# RN2483_breakout.net
KiCad netlist of a schematic drawn in Altium Designer
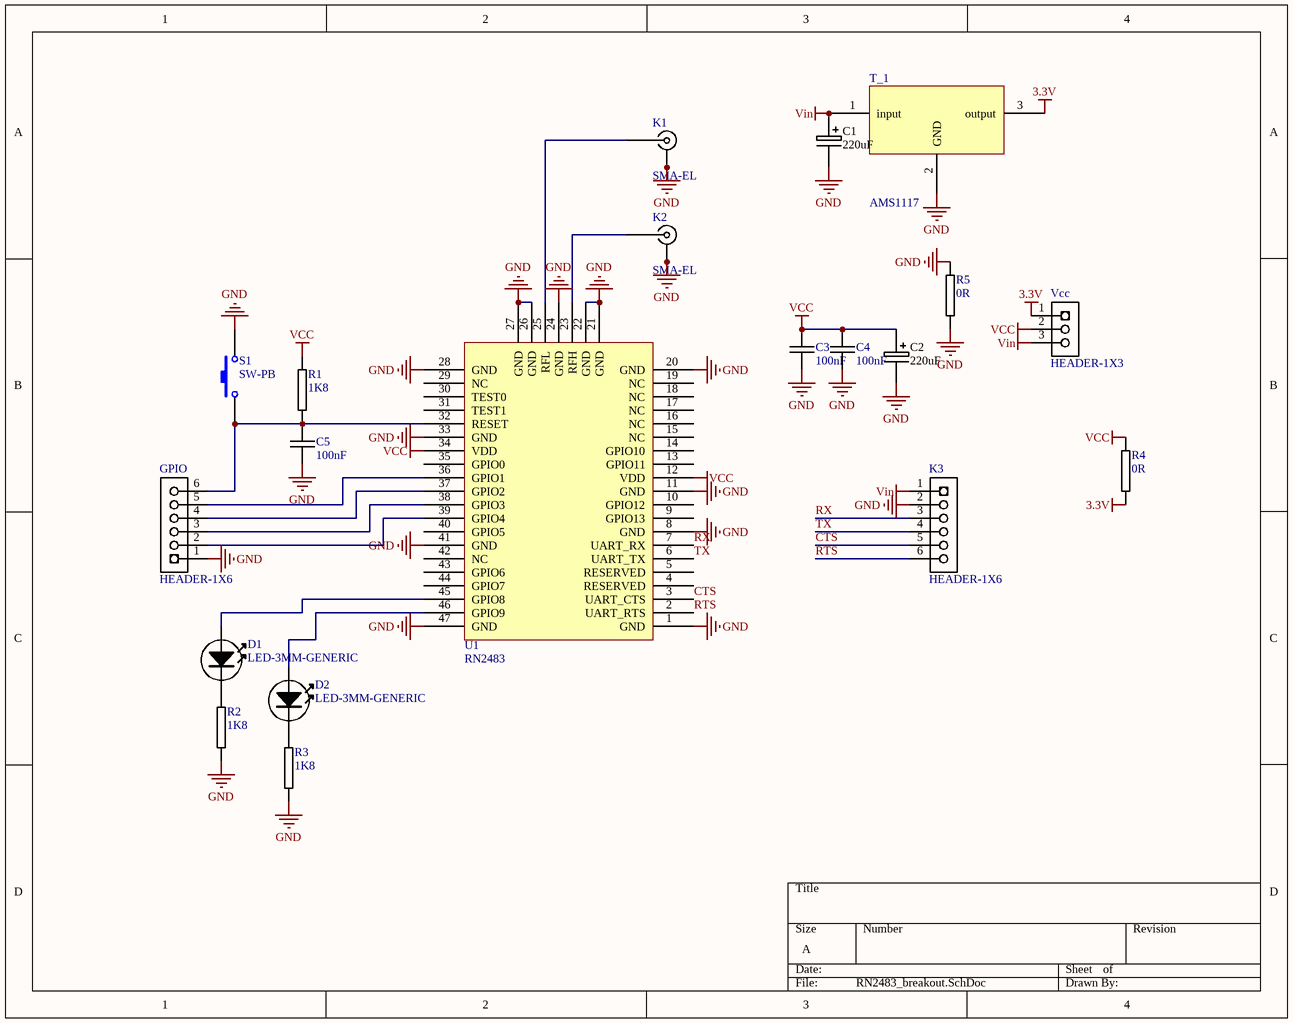
[diagram p0: RN2483_breakout.SchDoc]

(export (version "E")
  (design (tool "Eeschema 10.0.6"))
  (components
    (comp (ref "C1")
      (value "220uF")
      (footprint "TANTAL_SIZEA")
      (description "CAPACITOR POLARISED")
      (libsource (lib "vh_altium_library") (part "220UF-5MM"))
    )
    (comp (ref "C2")
      (value "220uF")
      (footprint "TANTAL_SIZEA")
      (description "CAPACITOR POLARISED")
      (libsource (lib "vh_altium_library") (part "220UF-5MM"))
    )
    (comp (ref "C3")
      (value "100nF")
      (footprint "0805C-GENERIC")
      (description "CAPACITOR 0805 CERAMIC")
      (fields (field (name "TOLERANCE") "±20%") (field (name "MANUFACTURER") "Panasonic - ECG"))
      (libsource (lib "vh_altium_library") (part "0805C-10UF-6V3-X5R-PAN"))
    )
    (comp (ref "C4")
      (value "100nF")
      (footprint "0805C-GENERIC")
      (description "CAPACITOR 0805 CERAMIC")
      (fields (field (name "TOLERANCE") "±20%") (field (name "MANUFACTURER") "Panasonic - ECG"))
      (libsource (lib "vh_altium_library") (part "0805C-10UF-6V3-X5R-PAN"))
    )
    (comp (ref "C5")
      (value "100nF")
      (footprint "0805C-GENERIC")
      (description "CAPACITOR 0805 CERAMIC")
      (fields (field (name "TOLERANCE") "±20%") (field (name "MANUFACTURER") "Panasonic - ECG"))
      (libsource (lib "vh_altium_library") (part "0805C-10UF-6V3-X5R-PAN"))
    )
    (comp (ref "D1")
      (value "LED-3MM-GENERIC")
      (footprint "0805R-GENERIC")
      (description "GENERIC LED 3MM")
      (libsource (lib "vh_altium_library") (part "LED-3MM-GENERIC"))
    )
    (comp (ref "D2")
      (value "LED-3MM-GENERIC")
      (footprint "0805R-GENERIC")
      (description "GENERIC LED 3MM")
      (libsource (lib "vh_altium_library") (part "LED-3MM-GENERIC"))
    )
    (comp (ref "GPIO")
      (value "HEADER-1X6")
      (footprint "HEADER-1X6")
      (libsource (lib "vh_altium_library") (part "HEADER-1X6"))
    )
    (comp (ref "K1")
      (value "SMA-EL")
      (footprint "SMA-ENDLAUNCH")
      (description "SMA THREADED RF CONNECTOR VERTICAL")
      (libsource (lib "vh_altium_library") (part "SMA-EL"))
    )
    (comp (ref "K2")
      (value "SMA-EL")
      (footprint "SMA-ENDLAUNCH")
      (description "SMA THREADED RF CONNECTOR VERTICAL")
      (libsource (lib "vh_altium_library") (part "SMA-EL"))
    )
    (comp (ref "K3")
      (value "HEADER-1X6")
      (footprint "HEADER-1X6")
      (libsource (lib "vh_altium_library") (part "HEADER-1X6"))
    )
    (comp (ref "R1")
      (value "1K8")
      (footprint "0805R-1K8")
      (description "RESISTOR 0805 1/4 WATT THIN FILM")
      (libsource (lib "vh_altium_library") (part "0805R-1K8"))
    )
    (comp (ref "R2")
      (value "1K8")
      (footprint "0805R-1K8")
      (description "RESISTOR 0805 1/4 WATT THIN FILM")
      (libsource (lib "vh_altium_library") (part "0805R-1K8"))
    )
    (comp (ref "R3")
      (value "1K8")
      (footprint "0805R-1K8")
      (description "RESISTOR 0805 1/4 WATT THIN FILM")
      (libsource (lib "vh_altium_library") (part "0805R-1K8"))
    )
    (comp (ref "R4")
      (value "0R")
      (footprint "0805R-GENERIC")
      (description "RESISTOR 0805 1 WATT")
      (libsource (lib "vh_altium_library") (part "0805R-0R"))
    )
    (comp (ref "R5")
      (value "0R")
      (footprint "0805R-GENERIC")
      (description "RESISTOR 0805 1 WATT")
      (libsource (lib "vh_altium_library") (part "0805R-0R"))
    )
    (comp (ref "S1")
      (value "SW-PB")
      (footprint "SW")
      (description "Switch")
      (fields (field (name "PUBLISHER") "Altium Limited"))
      (libsource (lib "Miscellaneous Devices") (part "SW-PB"))
    )
    (comp (ref "T_1")
      (value "AMS1117")
      (footprint "SOT-223B_M")
      (description "Voltage Regulator")
      (libsource (lib "MAX4644") (part "LM7815"))
    )
    (comp (ref "U1")
      (value "RN2483")
      (footprint "RN2483")
      (description "RN2483 - Microchip")
      (libsource (lib "RN2483_breakout_lib") (part "RN2483"))
    )
    (comp (ref "Vcc")
      (value "HEADER-1X3")
      (footprint "HEADER-1X3")
      (libsource (lib "vh_altium_library") (part "HEADER-1X3"))
    )
  )
  (nets
    (net (code "1") (name "/CTS") (class "Default")
      (node (ref "K3") (pin "5") (pintype "passive"))
      (node (ref "U1") (pin "3") (pinfunction "UART_CTS_3") (pintype "passive"))
    )
    (net (code "2") (name "/RTS") (class "Default")
      (node (ref "K3") (pin "6") (pintype "passive"))
      (node (ref "U1") (pin "2") (pinfunction "UART_RTS_2") (pintype "passive"))
    )
    (net (code "3") (name "/RX") (class "Default")
      (node (ref "K3") (pin "3") (pintype "passive"))
      (node (ref "U1") (pin "7") (pinfunction "UART_RX_7") (pintype "passive"))
    )
    (net (code "4") (name "/TX") (class "Default")
      (node (ref "K3") (pin "4") (pintype "passive"))
      (node (ref "U1") (pin "6") (pinfunction "UART_TX_6") (pintype "passive"))
    )
    (net (code "5") (name "3.3V") (class "Default")
      (node (ref "R4") (pin "2") (pintype "passive"))
      (node (ref "T_1") (pin "3") (pinfunction "output_3") (pintype "passive"))
      (node (ref "Vcc") (pin "1") (pintype "passive"))
    )
    (net (code "6") (name "GND") (class "Default")
      (node (ref "C1") (pin "-") (pinfunction "-_-") (pintype "passive"))
      (node (ref "C2") (pin "-") (pinfunction "-_-") (pintype "passive"))
      (node (ref "C3") (pin "2") (pintype "passive"))
      (node (ref "C4") (pin "2") (pintype "passive"))
      (node (ref "C5") (pin "2") (pintype "passive"))
      (node (ref "GPIO") (pin "1") (pintype "passive"))
      (node (ref "K1") (pin "2") (pinfunction "2_2") (pintype "passive"))
      (node (ref "K1") (pin "3") (pinfunction "3_3") (pintype "passive"))
      (node (ref "K1") (pin "4") (pinfunction "4_4") (pintype "passive"))
      (node (ref "K1") (pin "5") (pinfunction "5_5") (pintype "passive"))
      (node (ref "K2") (pin "2") (pinfunction "2_2") (pintype "passive"))
      (node (ref "K2") (pin "3") (pinfunction "3_3") (pintype "passive"))
      (node (ref "K2") (pin "4") (pinfunction "4_4") (pintype "passive"))
      (node (ref "K2") (pin "5") (pinfunction "5_5") (pintype "passive"))
      (node (ref "K3") (pin "2") (pintype "passive"))
      (node (ref "R2") (pin "2") (pintype "passive"))
      (node (ref "R3") (pin "2") (pintype "passive"))
      (node (ref "R5") (pin "1") (pintype "passive"))
      (node (ref "R5") (pin "2") (pintype "passive"))
      (node (ref "S1") (pin "2") (pinfunction "2_2") (pintype "passive"))
      (node (ref "T_1") (pin "2") (pinfunction "GND_2") (pintype "passive"))
      (node (ref "U1") (pin "1") (pinfunction "GND_1") (pintype "passive"))
      (node (ref "U1") (pin "11") (pinfunction "GND_11") (pintype "passive"))
      (node (ref "U1") (pin "20") (pinfunction "GND_20") (pintype "passive"))
      (node (ref "U1") (pin "21") (pinfunction "GND_21") (pintype "passive"))
      (node (ref "U1") (pin "22") (pinfunction "GND_22") (pintype "passive"))
      (node (ref "U1") (pin "24") (pinfunction "GND_24") (pintype "passive"))
      (node (ref "U1") (pin "26") (pinfunction "GND_26") (pintype "passive"))
      (node (ref "U1") (pin "27") (pinfunction "GND_27") (pintype "passive"))
      (node (ref "U1") (pin "28") (pinfunction "GND_28") (pintype "passive"))
      (node (ref "U1") (pin "33") (pinfunction "GND_33") (pintype "passive"))
      (node (ref "U1") (pin "41") (pinfunction "GND_41") (pintype "passive"))
      (node (ref "U1") (pin "47") (pinfunction "GND_47") (pintype "passive"))
      (node (ref "U1") (pin "8") (pinfunction "GND_8") (pintype "passive"))
    )
    (net (code "7") (name "Net-(D1-PadK)") (class "Default")
      (node (ref "D1") (pin "K") (pintype "passive"))
      (node (ref "R2") (pin "1") (pintype "passive"))
    )
    (net (code "8") (name "Net-(D2-PadK)") (class "Default")
      (node (ref "D2") (pin "K") (pintype "passive"))
      (node (ref "R3") (pin "1") (pintype "passive"))
    )
    (net (code "9") (name "Net-(U1-GPIO1)") (class "Default")
      (node (ref "GPIO") (pin "5") (pintype "passive"))
      (node (ref "U1") (pin "36") (pinfunction "GPIO1_36") (pintype "passive"))
    )
    (net (code "10") (name "Net-(U1-GPIO2)") (class "Default")
      (node (ref "GPIO") (pin "4") (pintype "passive"))
      (node (ref "U1") (pin "37") (pinfunction "GPIO2_37") (pintype "passive"))
    )
    (net (code "11") (name "Net-(U1-GPIO3)") (class "Default")
      (node (ref "GPIO") (pin "3") (pintype "passive"))
      (node (ref "U1") (pin "38") (pinfunction "GPIO3_38") (pintype "passive"))
    )
    (net (code "12") (name "Net-(U1-GPIO4)") (class "Default")
      (node (ref "GPIO") (pin "2") (pintype "passive"))
      (node (ref "U1") (pin "39") (pinfunction "GPIO4_39") (pintype "passive"))
    )
    (net (code "13") (name "Net-(U1-GPIO8)") (class "Default")
      (node (ref "D1") (pin "A") (pintype "passive"))
      (node (ref "U1") (pin "45") (pinfunction "GPIO8_45") (pintype "passive"))
    )
    (net (code "14") (name "Net-(U1-GPIO9)") (class "Default")
      (node (ref "D2") (pin "A") (pintype "passive"))
      (node (ref "U1") (pin "46") (pinfunction "GPIO9_46") (pintype "passive"))
    )
    (net (code "15") (name "Net-(U1-RESET)") (class "Default")
      (node (ref "C5") (pin "1") (pintype "passive"))
      (node (ref "GPIO") (pin "6") (pintype "passive"))
      (node (ref "R1") (pin "2") (pintype "passive"))
      (node (ref "S1") (pin "1") (pinfunction "1_1") (pintype "passive"))
      (node (ref "U1") (pin "32") (pinfunction "RESET_32") (pintype "passive"))
    )
    (net (code "16") (name "Net-(U1-RFH)") (class "Default")
      (node (ref "K2") (pin "1") (pinfunction "1_1") (pintype "passive"))
      (node (ref "U1") (pin "23") (pinfunction "RFH_23") (pintype "passive"))
    )
    (net (code "17") (name "Net-(U1-RFL)") (class "Default")
      (node (ref "K1") (pin "1") (pinfunction "1_1") (pintype "passive"))
      (node (ref "U1") (pin "25") (pinfunction "RFL_25") (pintype "passive"))
    )
    (net (code "18") (name "VCC") (class "Default")
      (node (ref "C2") (pin "+") (pinfunction "+_+") (pintype "passive"))
      (node (ref "C3") (pin "1") (pintype "passive"))
      (node (ref "C4") (pin "1") (pintype "passive"))
      (node (ref "R1") (pin "1") (pintype "passive"))
      (node (ref "R4") (pin "1") (pintype "passive"))
      (node (ref "U1") (pin "12") (pinfunction "VDD_12") (pintype "passive"))
      (node (ref "U1") (pin "34") (pinfunction "VDD_34") (pintype "passive"))
      (node (ref "Vcc") (pin "2") (pintype "passive"))
    )
    (net (code "19") (name "Vin") (class "Default")
      (node (ref "C1") (pin "+") (pinfunction "+_+") (pintype "passive"))
      (node (ref "K3") (pin "1") (pintype "passive"))
      (node (ref "T_1") (pin "1") (pinfunction "input_1") (pintype "passive"))
      (node (ref "Vcc") (pin "3") (pintype "passive"))
    )
    (net (code "20") (name "unconnected-(U1-GPIO0-Pad35)") (class "Default")
      (node (ref "U1") (pin "35") (pinfunction "GPIO0_35") (pintype "passive"))
    )
    (net (code "21") (name "unconnected-(U1-GPIO5-Pad40)") (class "Default")
      (node (ref "U1") (pin "40") (pinfunction "GPIO5_40") (pintype "passive"))
    )
    (net (code "22") (name "unconnected-(U1-GPIO6-Pad43)") (class "Default")
      (node (ref "U1") (pin "43") (pinfunction "GPIO6_43") (pintype "passive"))
    )
    (net (code "23") (name "unconnected-(U1-GPIO7-Pad44)") (class "Default")
      (node (ref "U1") (pin "44") (pinfunction "GPIO7_44") (pintype "passive"))
    )
    (net (code "24") (name "unconnected-(U1-GPIO10-Pad14)") (class "Default")
      (node (ref "U1") (pin "14") (pinfunction "GPIO10_14") (pintype "passive"))
    )
    (net (code "25") (name "unconnected-(U1-GPIO11-Pad13)") (class "Default")
      (node (ref "U1") (pin "13") (pinfunction "GPIO11_13") (pintype "passive"))
    )
    (net (code "26") (name "unconnected-(U1-GPIO12-Pad10)") (class "Default")
      (node (ref "U1") (pin "10") (pinfunction "GPIO12_10") (pintype "passive"))
    )
    (net (code "27") (name "unconnected-(U1-GPIO13-Pad9)") (class "Default")
      (node (ref "U1") (pin "9") (pinfunction "GPIO13_9") (pintype "passive"))
    )
    (net (code "28") (name "unconnected-(U1-NC-Pad15)") (class "Default")
      (node (ref "U1") (pin "15") (pinfunction "NC_15") (pintype "passive"))
    )
    (net (code "29") (name "unconnected-(U1-NC-Pad16)") (class "Default")
      (node (ref "U1") (pin "16") (pinfunction "NC_16") (pintype "passive"))
    )
    (net (code "30") (name "unconnected-(U1-NC-Pad17)") (class "Default")
      (node (ref "U1") (pin "17") (pinfunction "NC_17") (pintype "passive"))
    )
    (net (code "31") (name "unconnected-(U1-NC-Pad18)") (class "Default")
      (node (ref "U1") (pin "18") (pinfunction "NC_18") (pintype "passive"))
    )
    (net (code "32") (name "unconnected-(U1-NC-Pad19)") (class "Default")
      (node (ref "U1") (pin "19") (pinfunction "NC_19") (pintype "passive"))
    )
    (net (code "33") (name "unconnected-(U1-NC-Pad29)") (class "Default")
      (node (ref "U1") (pin "29") (pinfunction "NC_29") (pintype "passive"))
    )
    (net (code "34") (name "unconnected-(U1-NC-Pad42)") (class "Default")
      (node (ref "U1") (pin "42") (pinfunction "NC_42") (pintype "passive"))
    )
    (net (code "35") (name "unconnected-(U1-RESERVED-Pad4)") (class "Default")
      (node (ref "U1") (pin "4") (pinfunction "RESERVED_4") (pintype "passive"))
    )
    (net (code "36") (name "unconnected-(U1-RESERVED-Pad5)") (class "Default")
      (node (ref "U1") (pin "5") (pinfunction "RESERVED_5") (pintype "passive"))
    )
    (net (code "37") (name "unconnected-(U1-TEST0-Pad30)") (class "Default")
      (node (ref "U1") (pin "30") (pinfunction "TEST0_30") (pintype "passive"))
    )
    (net (code "38") (name "unconnected-(U1-TEST1-Pad31)") (class "Default")
      (node (ref "U1") (pin "31") (pinfunction "TEST1_31") (pintype "passive"))
    )
  )
)
